# receiver.net
KiCad netlist of a schematic drawn in EAGLE
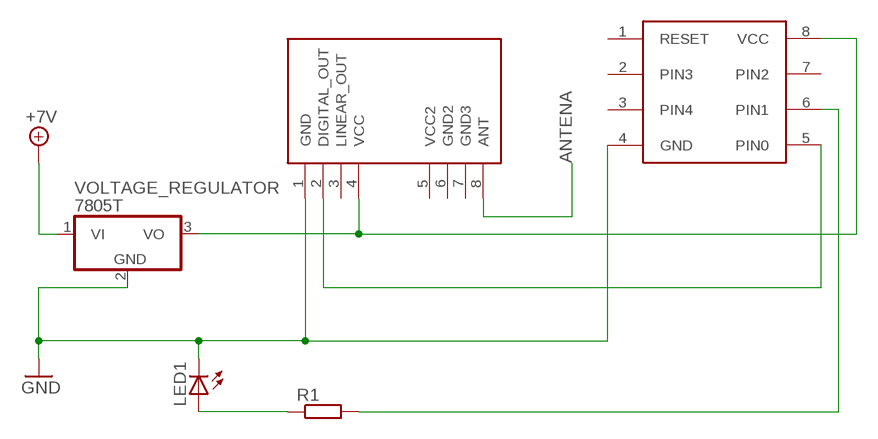
[diagram p0: schematic, sheet 1]

(export (version "E")
  (design (tool "Eeschema 10.0.6"))
  (components
    (comp (ref "LED1")
      (value "LED")
      (footprint "eagle-import:SMARTLED-TTW")
      (libsource (lib "eagle-import") (part "LED"))
    )
    (comp (ref "R1")
      (value "R-EU_0204/2V")
      (footprint "eagle-import:0204V")
      (libsource (lib "eagle-import") (part "R-EU_0204/2V"))
    )
    (comp (ref "U$1")
      (value "WRL-10533")
      (footprint "eagle-import:WRL-10533")
      (libsource (lib "eagle-import") (part "WRL-10533"))
    )
    (comp (ref "U$2")
      (value "ATTINY85")
      (footprint "eagle-import:ATTINY85")
      (libsource (lib "eagle-import") (part "ATTINY85"))
    )
    (comp (ref "VOLTAGE_REGULATOR")
      (value "7805T")
      (footprint "eagle-import:TO220H")
      (libsource (lib "eagle-import") (part "78T05"))
    )
  )
  (nets
    (net (code "1") (name "+7V") (class "Default")
      (node (ref "VOLTAGE_REGULATOR") (pin "1") (pinfunction "VI_1") (pintype "input"))
    )
    (net (code "2") (name "/ANTENA") (class "Default")
      (node (ref "U$1") (pin "8") (pinfunction "ANT_8") (pintype "bidirectional"))
    )
    (net (code "3") (name "GND") (class "Default")
      (node (ref "LED1") (pin "C@1") (pinfunction "C_C@1") (pintype "passive"))
      (node (ref "U$1") (pin "1") (pinfunction "GND_1") (pintype "bidirectional"))
      (node (ref "U$2") (pin "4") (pinfunction "GND_4") (pintype "bidirectional"))
      (node (ref "VOLTAGE_REGULATOR") (pin "2") (pinfunction "GND_2") (pintype "passive"))
    )
    (net (code "4") (name "Net-(LED1-A)") (class "Default")
      (node (ref "LED1") (pin "A@1") (pinfunction "A_A@1") (pintype "passive"))
      (node (ref "R1") (pin "1") (pinfunction "1_1") (pintype "passive"))
    )
    (net (code "5") (name "Net-(U$1-DIGITAL_OUT)") (class "Default")
      (node (ref "U$1") (pin "2") (pinfunction "DIGITAL_OUT_2") (pintype "bidirectional"))
      (node (ref "U$2") (pin "5") (pinfunction "PIN0_5") (pintype "bidirectional"))
    )
    (net (code "6") (name "Net-(U$1-VCC)") (class "Default")
      (node (ref "U$1") (pin "4") (pinfunction "VCC_4") (pintype "bidirectional"))
      (node (ref "U$2") (pin "8") (pinfunction "VCC_8") (pintype "bidirectional"))
      (node (ref "VOLTAGE_REGULATOR") (pin "3") (pinfunction "VO_3") (pintype "passive"))
    )
    (net (code "7") (name "Net-(U$2-PIN1)") (class "Default")
      (node (ref "R1") (pin "2") (pinfunction "2_2") (pintype "passive"))
      (node (ref "U$2") (pin "6") (pinfunction "PIN1_6") (pintype "bidirectional"))
    )
    (net (code "8") (name "unconnected-(U$1-GND2-Pad6)") (class "Default")
      (node (ref "U$1") (pin "6") (pinfunction "GND2_6") (pintype "bidirectional"))
    )
    (net (code "9") (name "unconnected-(U$1-GND3-Pad7)") (class "Default")
      (node (ref "U$1") (pin "7") (pinfunction "GND3_7") (pintype "bidirectional"))
    )
    (net (code "10") (name "unconnected-(U$1-LINEAR_OUT-Pad3)") (class "Default")
      (node (ref "U$1") (pin "3") (pinfunction "LINEAR_OUT_3") (pintype "bidirectional"))
    )
    (net (code "11") (name "unconnected-(U$1-VCC2-Pad5)") (class "Default")
      (node (ref "U$1") (pin "5") (pinfunction "VCC2_5") (pintype "bidirectional"))
    )
    (net (code "12") (name "unconnected-(U$2-PIN2-Pad7)") (class "Default")
      (node (ref "U$2") (pin "7") (pinfunction "PIN2_7") (pintype "bidirectional"))
    )
    (net (code "13") (name "unconnected-(U$2-PIN3-Pad2)") (class "Default")
      (node (ref "U$2") (pin "2") (pinfunction "PIN3_2") (pintype "bidirectional"))
    )
    (net (code "14") (name "unconnected-(U$2-PIN4-Pad3)") (class "Default")
      (node (ref "U$2") (pin "3") (pinfunction "PIN4_3") (pintype "bidirectional"))
    )
    (net (code "15") (name "unconnected-(U$2-RESET-Pad1)") (class "Default")
      (node (ref "U$2") (pin "1") (pinfunction "RESET_1") (pintype "bidirectional"))
    )
  )
)
